# Sync_Rectifier_v0_1.net
KiCad netlist of a schematic drawn in Altium Designer
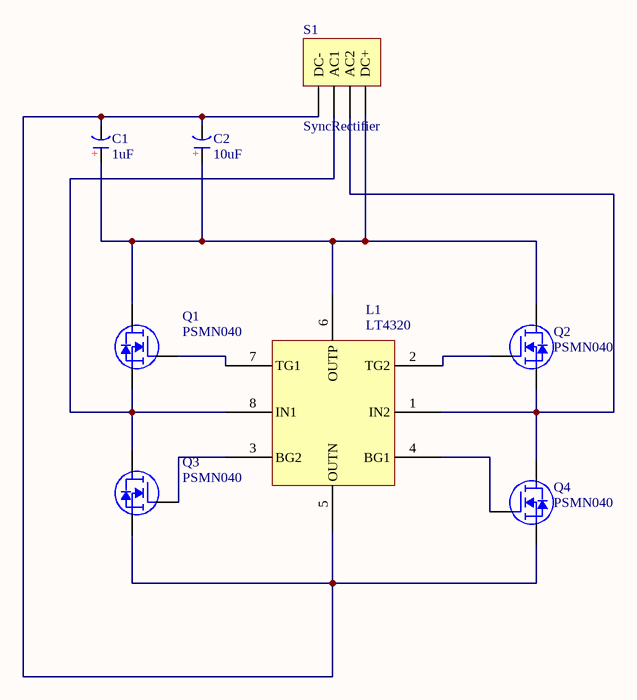
[diagram p0: Sync_Rectifier_v0.1.SchDoc]

(export (version "E")
  (design (tool "Eeschema 10.0.6"))
  (components
    (comp (ref "C1")
      (value "1uF")
      (footprint "C 0805")
      (description "贴片钽电容")
      (fields (field (name "版权归属") "源创客"))
      (libsource (lib "电阻-电容-电感") (part "C-CD"))
    )
    (comp (ref "C2")
      (value "10uF")
      (footprint "2220")
      (description "贴片钽电容")
      (fields (field (name "版权归属") "源创客"))
      (libsource (lib "电阻-电容-电感") (part "C-CD"))
    )
    (comp (ref "L1")
      (value "LT4320")
      (footprint "DIP-8")
      (description "Ideal Diode Bridge Controller")
      (libsource (lib "二极管-整流桥") (part "LT4320"))
    )
    (comp (ref "Q1")
      (value "PSMN040")
      (footprint "SOT-1210-BL")
      (description "N-channel 100 V 36.6 mΩ standard level MOSFET")
      (libsource (lib "场效应管") (part "PSMN040-100MSE"))
    )
    (comp (ref "Q2")
      (value "PSMN040")
      (footprint "SOT-1210-BL")
      (description "N-channel 100 V 36.6 mΩ standard level MOSFET")
      (libsource (lib "场效应管") (part "PSMN040-100MSE"))
    )
    (comp (ref "Q3")
      (value "PSMN040")
      (footprint "SOT-1210-BL")
      (description "N-channel 100 V 36.6 mΩ standard level MOSFET")
      (libsource (lib "场效应管") (part "PSMN040-100MSE"))
    )
    (comp (ref "Q4")
      (value "PSMN040")
      (footprint "SOT-1210-BL")
      (description "N-channel 100 V 36.6 mΩ standard level MOSFET")
      (libsource (lib "场效应管") (part "PSMN040-100MSE"))
    )
    (comp (ref "S1")
      (value "SyncRectifier")
      (footprint "GBU")
      (libsource (lib "Connectors") (part "SyncRectifier"))
    )
  )
  (nets
    (net (code "1") (name "Net-(C1-A)") (class "Default")
      (node (ref "C1") (pin "1") (pinfunction "A_1") (pintype "passive"))
      (node (ref "C2") (pin "1") (pinfunction "A_1") (pintype "passive"))
      (node (ref "L1") (pin "6") (pinfunction "OUTP_6") (pintype "passive"))
      (node (ref "Q1") (pin "3") (pinfunction "D_3") (pintype "passive"))
      (node (ref "Q2") (pin "3") (pinfunction "D_3") (pintype "passive"))
      (node (ref "S1") (pin "4") (pinfunction "DC+_4") (pintype "passive"))
    )
    (net (code "2") (name "Net-(C1-K)") (class "Default")
      (node (ref "C1") (pin "2") (pinfunction "K_2") (pintype "passive"))
      (node (ref "C2") (pin "2") (pinfunction "K_2") (pintype "passive"))
      (node (ref "L1") (pin "5") (pinfunction "OUTN_5") (pintype "passive"))
      (node (ref "Q3") (pin "1") (pinfunction "S_1") (pintype "passive"))
      (node (ref "Q4") (pin "1") (pinfunction "S_1") (pintype "passive"))
      (node (ref "S1") (pin "1") (pinfunction "DC-_1") (pintype "passive"))
    )
    (net (code "3") (name "Net-(L1-BG1)") (class "Default")
      (node (ref "L1") (pin "4") (pinfunction "BG1_4") (pintype "passive"))
      (node (ref "Q4") (pin "2") (pinfunction "G_2") (pintype "passive"))
    )
    (net (code "4") (name "Net-(L1-BG2)") (class "Default")
      (node (ref "L1") (pin "3") (pinfunction "BG2_3") (pintype "passive"))
      (node (ref "Q3") (pin "2") (pinfunction "G_2") (pintype "passive"))
    )
    (net (code "5") (name "Net-(L1-IN1)") (class "Default")
      (node (ref "L1") (pin "8") (pinfunction "IN1_8") (pintype "passive"))
      (node (ref "Q1") (pin "1") (pinfunction "S_1") (pintype "passive"))
      (node (ref "Q3") (pin "3") (pinfunction "D_3") (pintype "passive"))
      (node (ref "S1") (pin "2") (pinfunction "AC1_2") (pintype "passive"))
    )
    (net (code "6") (name "Net-(L1-IN2)") (class "Default")
      (node (ref "L1") (pin "1") (pinfunction "IN2_1") (pintype "passive"))
      (node (ref "Q2") (pin "1") (pinfunction "S_1") (pintype "passive"))
      (node (ref "Q4") (pin "3") (pinfunction "D_3") (pintype "passive"))
      (node (ref "S1") (pin "3") (pinfunction "AC2_3") (pintype "passive"))
    )
    (net (code "7") (name "Net-(L1-TG1)") (class "Default")
      (node (ref "L1") (pin "7") (pinfunction "TG1_7") (pintype "passive"))
      (node (ref "Q1") (pin "2") (pinfunction "G_2") (pintype "passive"))
    )
    (net (code "8") (name "Net-(L1-TG2)") (class "Default")
      (node (ref "L1") (pin "2") (pinfunction "TG2_2") (pintype "passive"))
      (node (ref "Q2") (pin "2") (pinfunction "G_2") (pintype "passive"))
    )
  )
)
